# Chaoticvolt-4_digit_7seg_display.net
KiCad netlist of a schematic drawn in EasyEDA Pro
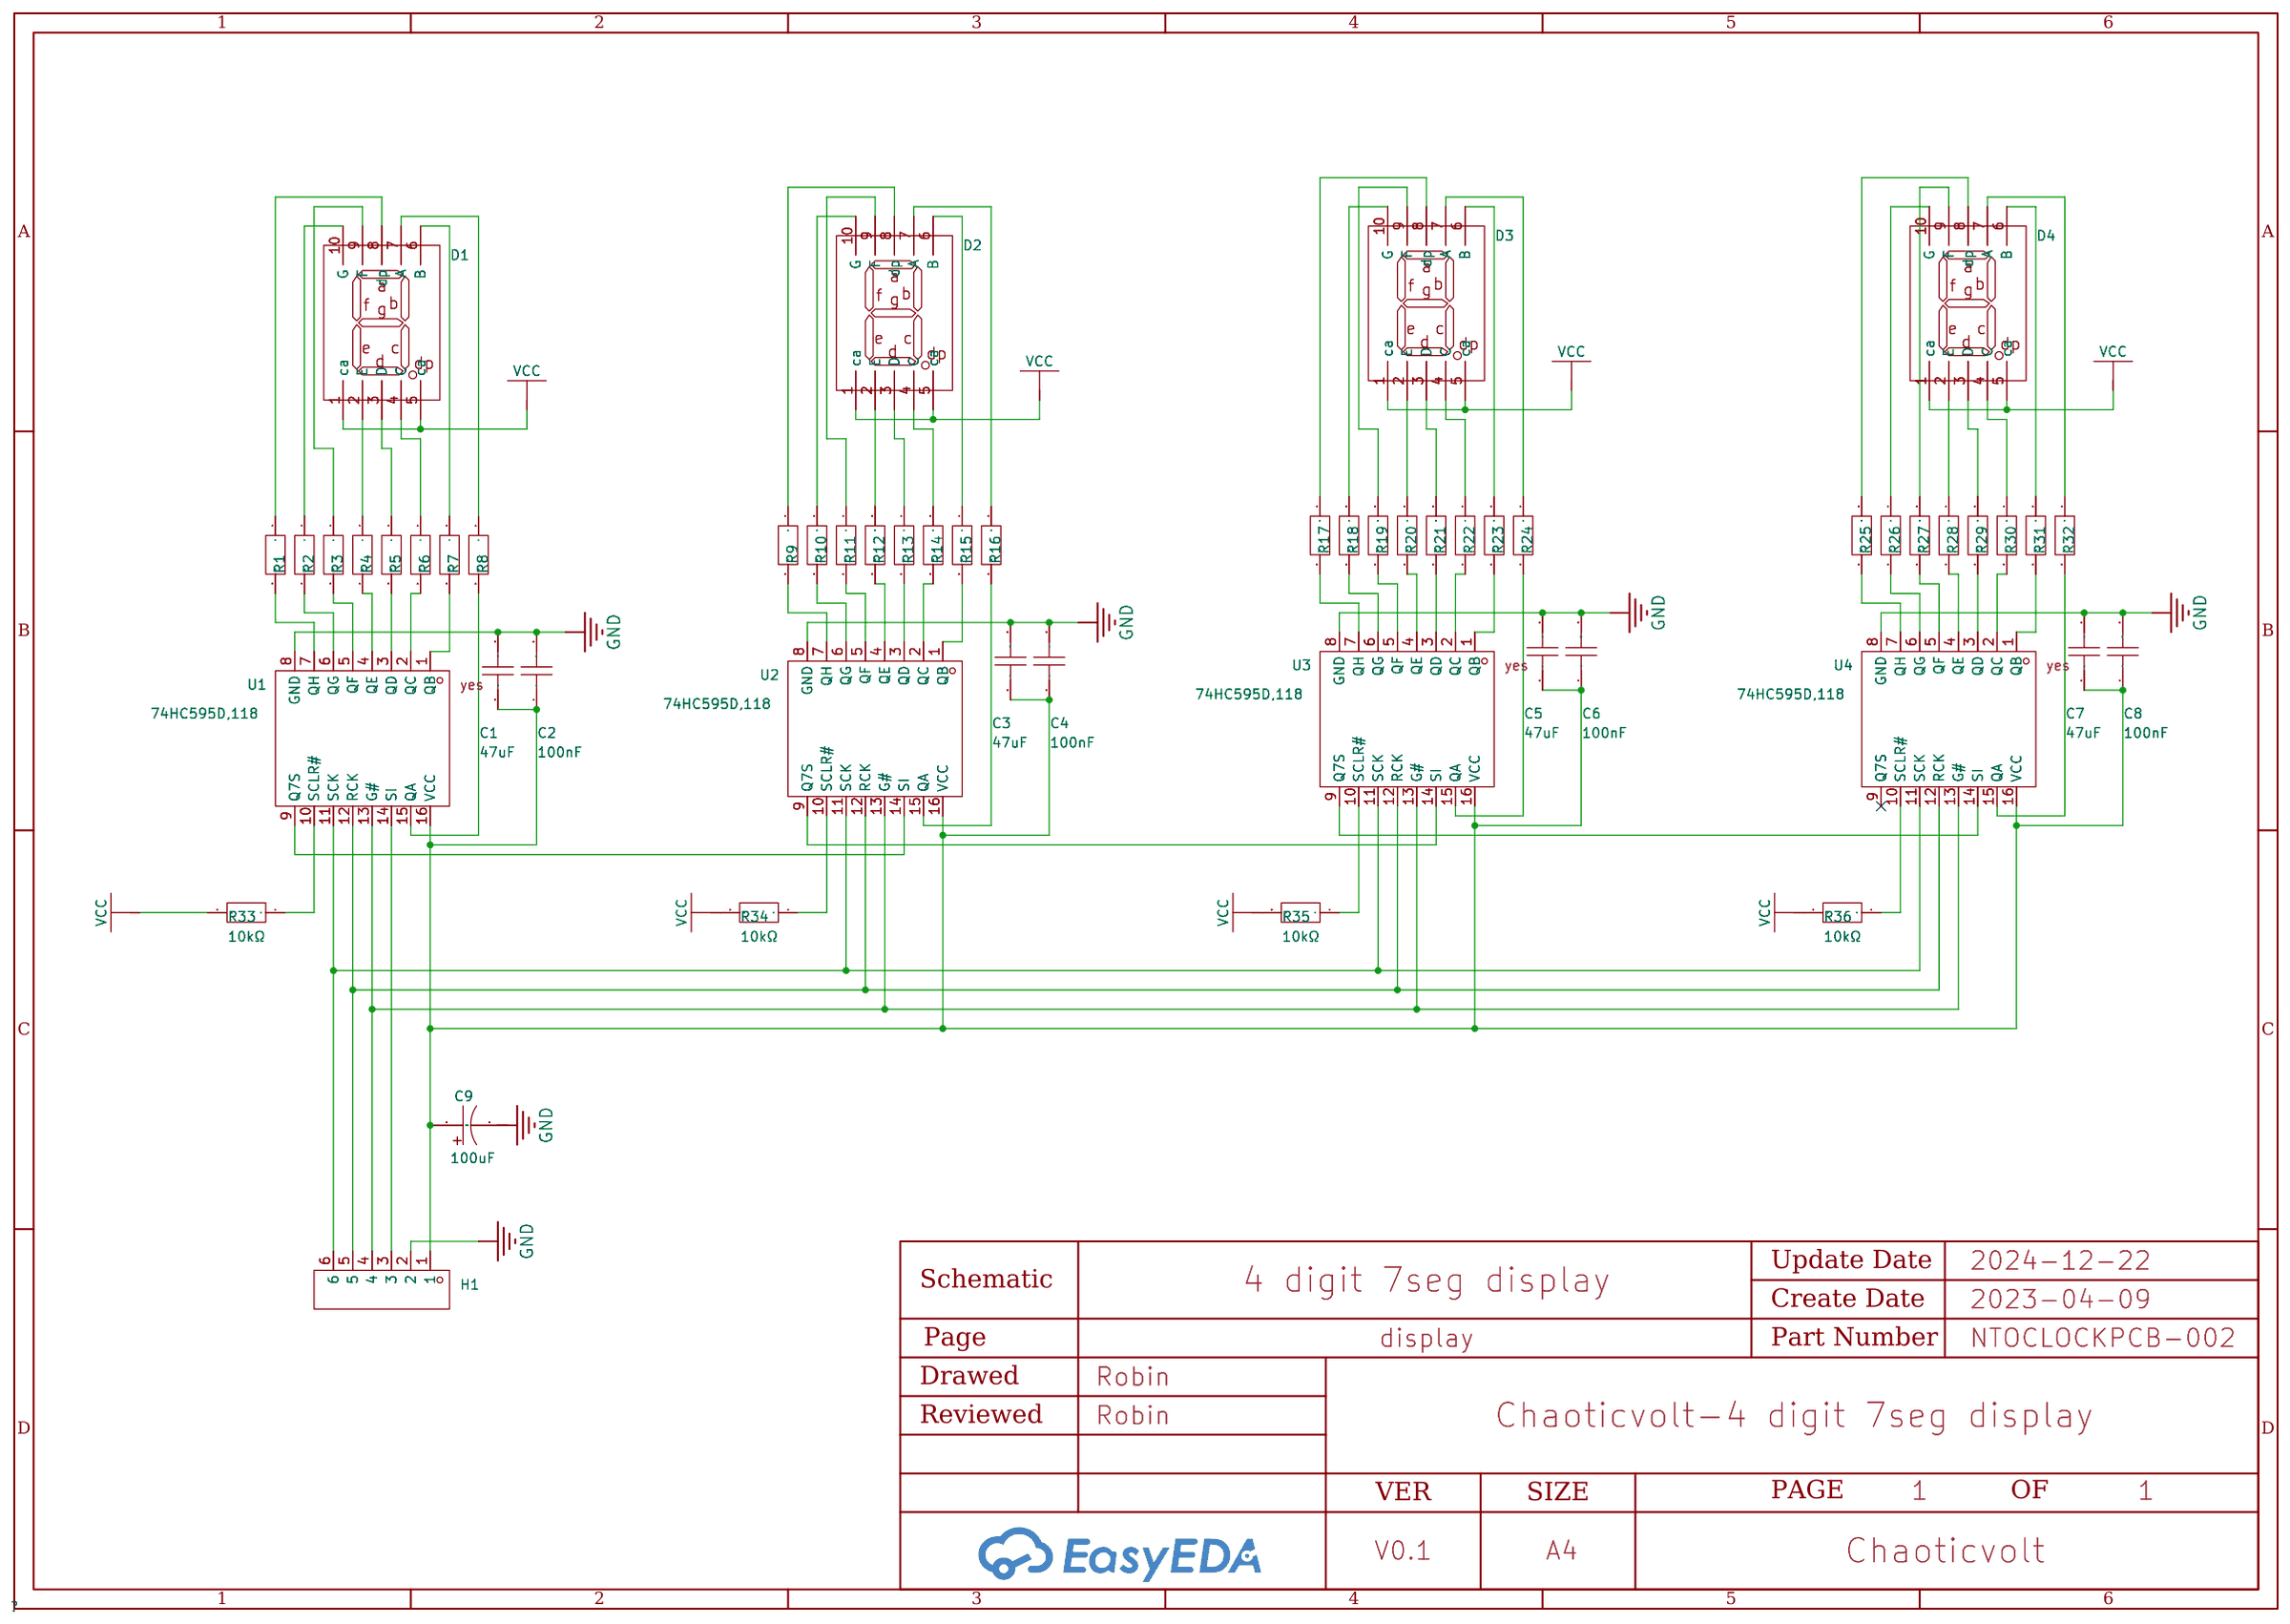
[diagram p0: schematic sheet]

(export (version "E")
  (design (tool "Eeschema 10.0.6"))
  (components
    (comp (ref "C1")
      (value "47uF")
      (footprint "easyedapro:C1206")
      (fields
        (field (name "Manufacturer Part") "CL31A476MPHNNNE")
        (field (name "Manufacturer") "SAMSUNG(三星)")
      )
      (libsource (lib "easyedapro") (part "CL31A476MPHNNNE"))
    )
    (comp (ref "C2")
      (value "100nF")
      (footprint "easyedapro:C1210")
      (fields
        (field (name "Manufacturer Part") "CL05B104KO5NNNC")
        (field (name "Manufacturer") "SAMSUNG(三星)")
      )
      (libsource (lib "easyedapro") (part "C1210C104K1RAC7800"))
    )
    (comp (ref "C3")
      (value "47uF")
      (footprint "easyedapro:C1206")
      (fields
        (field (name "Manufacturer Part") "CL31A476MPHNNNE")
        (field (name "Manufacturer") "SAMSUNG(三星)")
      )
      (libsource (lib "easyedapro") (part "CL31A476MPHNNNE"))
    )
    (comp (ref "C4")
      (value "100nF")
      (footprint "easyedapro:C1210")
      (fields
        (field (name "Manufacturer Part") "CL05B104KO5NNNC")
        (field (name "Manufacturer") "SAMSUNG(三星)")
      )
      (libsource (lib "easyedapro") (part "C1210C104K1RAC7800"))
    )
    (comp (ref "C5")
      (value "47uF")
      (footprint "easyedapro:C1206")
      (fields
        (field (name "Manufacturer Part") "CL31A476MPHNNNE")
        (field (name "Manufacturer") "SAMSUNG(三星)")
      )
      (libsource (lib "easyedapro") (part "CL31A476MPHNNNE"))
    )
    (comp (ref "C6")
      (value "100nF")
      (footprint "easyedapro:C1210")
      (fields
        (field (name "Manufacturer Part") "CL05B104KO5NNNC")
        (field (name "Manufacturer") "SAMSUNG(三星)")
      )
      (libsource (lib "easyedapro") (part "C1210C104K1RAC7800"))
    )
    (comp (ref "C7")
      (value "47uF")
      (footprint "easyedapro:C1206")
      (fields
        (field (name "Manufacturer Part") "CL31A476MPHNNNE")
        (field (name "Manufacturer") "SAMSUNG(三星)")
      )
      (libsource (lib "easyedapro") (part "CL31A476MPHNNNE"))
    )
    (comp (ref "C8")
      (value "100nF")
      (footprint "easyedapro:C1210")
      (fields
        (field (name "Manufacturer Part") "CL05B104KO5NNNC")
        (field (name "Manufacturer") "SAMSUNG(三星)")
      )
      (libsource (lib "easyedapro") (part "C1210C104K1RAC7800"))
    )
    (comp (ref "C9")
      (value "100uF")
      (footprint "easyedapro:CAP-SMD_L3.5-W2.8-R-RD")
      (fields
        (field (name "Manufacturer Part") "CA45-B-10V-100uF-M")
        (field (name "Manufacturer") "CEC(振华新云)")
      )
      (libsource (lib "easyedapro") (part "CA45-B-10V-100UF-M"))
    )
    (comp (ref "D1")
      (value "~")
      (footprint "easyedapro:FJS12101")
      (libsource (lib "easyedapro") (part "FJS12101"))
    )
    (comp (ref "D2")
      (value "~")
      (footprint "easyedapro:FJS12101")
      (libsource (lib "easyedapro") (part "FJS12101"))
    )
    (comp (ref "D3")
      (value "~")
      (footprint "easyedapro:FJS12101")
      (libsource (lib "easyedapro") (part "FJS12101"))
    )
    (comp (ref "D4")
      (value "~")
      (footprint "easyedapro:FJS12101")
      (libsource (lib "easyedapro") (part "FJS12101"))
    )
    (comp (ref "H1")
      (value "~")
      (footprint "easyedapro:HDR-TH_6P-P2.54-V_Z-211-0611-0021-001")
      (fields (field (name "Manufacturer Part") "PZ254R-11-06P") (field (name "Manufacturer") "XFCN(兴飞)"))
      (libsource (lib "easyedapro") (part "PZ254R-11-06P"))
    )
    (comp (ref "R1")
      (value "100Ω")
      (footprint "easyedapro:R1210")
      (fields
        (field (name "Manufacturer Part") "0805W8F1000T5E")
        (field (name "Manufacturer") "UNI-ROYAL(厚声)")
      )
      (libsource (lib "easyedapro") (part "RK73H2ETTD2700F"))
    )
    (comp (ref "R2")
      (value "100Ω")
      (footprint "easyedapro:R1210")
      (fields
        (field (name "Manufacturer Part") "0805W8F1000T5E")
        (field (name "Manufacturer") "UNI-ROYAL(厚声)")
      )
      (libsource (lib "easyedapro") (part "RK73H2ETTD2700F"))
    )
    (comp (ref "R3")
      (value "100Ω")
      (footprint "easyedapro:R1210")
      (fields
        (field (name "Manufacturer Part") "0805W8F1000T5E")
        (field (name "Manufacturer") "UNI-ROYAL(厚声)")
      )
      (libsource (lib "easyedapro") (part "RK73H2ETTD2700F"))
    )
    (comp (ref "R4")
      (value "100Ω")
      (footprint "easyedapro:R1210")
      (fields
        (field (name "Manufacturer Part") "0805W8F1000T5E")
        (field (name "Manufacturer") "UNI-ROYAL(厚声)")
      )
      (libsource (lib "easyedapro") (part "RK73H2ETTD2700F"))
    )
    (comp (ref "R5")
      (value "100Ω")
      (footprint "easyedapro:R1210")
      (fields
        (field (name "Manufacturer Part") "0805W8F1000T5E")
        (field (name "Manufacturer") "UNI-ROYAL(厚声)")
      )
      (libsource (lib "easyedapro") (part "RK73H2ETTD2700F"))
    )
    (comp (ref "R6")
      (value "100Ω")
      (footprint "easyedapro:R1210")
      (fields
        (field (name "Manufacturer Part") "0805W8F1000T5E")
        (field (name "Manufacturer") "UNI-ROYAL(厚声)")
      )
      (libsource (lib "easyedapro") (part "RK73H2ETTD2700F"))
    )
    (comp (ref "R7")
      (value "100Ω")
      (footprint "easyedapro:R1210")
      (fields
        (field (name "Manufacturer Part") "0805W8F1000T5E")
        (field (name "Manufacturer") "UNI-ROYAL(厚声)")
      )
      (libsource (lib "easyedapro") (part "RK73H2ETTD2700F"))
    )
    (comp (ref "R8")
      (value "100Ω")
      (footprint "easyedapro:R1210")
      (fields
        (field (name "Manufacturer Part") "0805W8F1000T5E")
        (field (name "Manufacturer") "UNI-ROYAL(厚声)")
      )
      (libsource (lib "easyedapro") (part "RK73H2ETTD2700F"))
    )
    (comp (ref "R9")
      (value "100Ω")
      (footprint "easyedapro:R1210")
      (fields
        (field (name "Manufacturer Part") "0805W8F1000T5E")
        (field (name "Manufacturer") "UNI-ROYAL(厚声)")
      )
      (libsource (lib "easyedapro") (part "RK73H2ETTD2700F"))
    )
    (comp (ref "R10")
      (value "100Ω")
      (footprint "easyedapro:R1210")
      (fields
        (field (name "Manufacturer Part") "0805W8F1000T5E")
        (field (name "Manufacturer") "UNI-ROYAL(厚声)")
      )
      (libsource (lib "easyedapro") (part "RK73H2ETTD2700F"))
    )
    (comp (ref "R11")
      (value "100Ω")
      (footprint "easyedapro:R1210")
      (fields
        (field (name "Manufacturer Part") "0805W8F1000T5E")
        (field (name "Manufacturer") "UNI-ROYAL(厚声)")
      )
      (libsource (lib "easyedapro") (part "RK73H2ETTD2700F"))
    )
    (comp (ref "R12")
      (value "100Ω")
      (footprint "easyedapro:R1210")
      (fields
        (field (name "Manufacturer Part") "0805W8F1000T5E")
        (field (name "Manufacturer") "UNI-ROYAL(厚声)")
      )
      (libsource (lib "easyedapro") (part "RK73H2ETTD2700F"))
    )
    (comp (ref "R13")
      (value "100Ω")
      (footprint "easyedapro:R1210")
      (fields
        (field (name "Manufacturer Part") "0805W8F1000T5E")
        (field (name "Manufacturer") "UNI-ROYAL(厚声)")
      )
      (libsource (lib "easyedapro") (part "RK73H2ETTD2700F"))
    )
    (comp (ref "R14")
      (value "100Ω")
      (footprint "easyedapro:R1210")
      (fields
        (field (name "Manufacturer Part") "0805W8F1000T5E")
        (field (name "Manufacturer") "UNI-ROYAL(厚声)")
      )
      (libsource (lib "easyedapro") (part "RK73H2ETTD2700F"))
    )
    (comp (ref "R15")
      (value "100Ω")
      (footprint "easyedapro:R1210")
      (fields
        (field (name "Manufacturer Part") "0805W8F1000T5E")
        (field (name "Manufacturer") "UNI-ROYAL(厚声)")
      )
      (libsource (lib "easyedapro") (part "RK73H2ETTD2700F"))
    )
    (comp (ref "R16")
      (value "100Ω")
      (footprint "easyedapro:R1210")
      (fields
        (field (name "Manufacturer Part") "0805W8F1000T5E")
        (field (name "Manufacturer") "UNI-ROYAL(厚声)")
      )
      (libsource (lib "easyedapro") (part "RK73H2ETTD2700F"))
    )
    (comp (ref "R17")
      (value "100Ω")
      (footprint "easyedapro:R1210")
      (fields
        (field (name "Manufacturer Part") "0805W8F1000T5E")
        (field (name "Manufacturer") "UNI-ROYAL(厚声)")
      )
      (libsource (lib "easyedapro") (part "RK73H2ETTD2700F"))
    )
    (comp (ref "R18")
      (value "100Ω")
      (footprint "easyedapro:R1210")
      (fields
        (field (name "Manufacturer Part") "0805W8F1000T5E")
        (field (name "Manufacturer") "UNI-ROYAL(厚声)")
      )
      (libsource (lib "easyedapro") (part "RK73H2ETTD2700F"))
    )
    (comp (ref "R19")
      (value "100Ω")
      (footprint "easyedapro:R1210")
      (fields
        (field (name "Manufacturer Part") "0805W8F1000T5E")
        (field (name "Manufacturer") "UNI-ROYAL(厚声)")
      )
      (libsource (lib "easyedapro") (part "RK73H2ETTD2700F"))
    )
    (comp (ref "R20")
      (value "100Ω")
      (footprint "easyedapro:R1210")
      (fields
        (field (name "Manufacturer Part") "0805W8F1000T5E")
        (field (name "Manufacturer") "UNI-ROYAL(厚声)")
      )
      (libsource (lib "easyedapro") (part "RK73H2ETTD2700F"))
    )
    (comp (ref "R21")
      (value "100Ω")
      (footprint "easyedapro:R1210")
      (fields
        (field (name "Manufacturer Part") "0805W8F1000T5E")
        (field (name "Manufacturer") "UNI-ROYAL(厚声)")
      )
      (libsource (lib "easyedapro") (part "RK73H2ETTD2700F"))
    )
    (comp (ref "R22")
      (value "100Ω")
      (footprint "easyedapro:R1210")
      (fields
        (field (name "Manufacturer Part") "0805W8F1000T5E")
        (field (name "Manufacturer") "UNI-ROYAL(厚声)")
      )
      (libsource (lib "easyedapro") (part "RK73H2ETTD2700F"))
    )
    (comp (ref "R23")
      (value "100Ω")
      (footprint "easyedapro:R1210")
      (fields
        (field (name "Manufacturer Part") "0805W8F1000T5E")
        (field (name "Manufacturer") "UNI-ROYAL(厚声)")
      )
      (libsource (lib "easyedapro") (part "RK73H2ETTD2700F"))
    )
    (comp (ref "R24")
      (value "100Ω")
      (footprint "easyedapro:R1210")
      (fields
        (field (name "Manufacturer Part") "0805W8F1000T5E")
        (field (name "Manufacturer") "UNI-ROYAL(厚声)")
      )
      (libsource (lib "easyedapro") (part "RK73H2ETTD2700F"))
    )
    (comp (ref "R25")
      (value "100Ω")
      (footprint "easyedapro:R1210")
      (fields
        (field (name "Manufacturer Part") "0805W8F1000T5E")
        (field (name "Manufacturer") "UNI-ROYAL(厚声)")
      )
      (libsource (lib "easyedapro") (part "RK73H2ETTD2700F"))
    )
    (comp (ref "R26")
      (value "100Ω")
      (footprint "easyedapro:R1210")
      (fields
        (field (name "Manufacturer Part") "0805W8F1000T5E")
        (field (name "Manufacturer") "UNI-ROYAL(厚声)")
      )
      (libsource (lib "easyedapro") (part "RK73H2ETTD2700F"))
    )
    (comp (ref "R27")
      (value "100Ω")
      (footprint "easyedapro:R1210")
      (fields
        (field (name "Manufacturer Part") "0805W8F1000T5E")
        (field (name "Manufacturer") "UNI-ROYAL(厚声)")
      )
      (libsource (lib "easyedapro") (part "RK73H2ETTD2700F"))
    )
    (comp (ref "R28")
      (value "100Ω")
      (footprint "easyedapro:R1210")
      (fields
        (field (name "Manufacturer Part") "0805W8F1000T5E")
        (field (name "Manufacturer") "UNI-ROYAL(厚声)")
      )
      (libsource (lib "easyedapro") (part "RK73H2ETTD2700F"))
    )
    (comp (ref "R29")
      (value "100Ω")
      (footprint "easyedapro:R1210")
      (fields
        (field (name "Manufacturer Part") "0805W8F1000T5E")
        (field (name "Manufacturer") "UNI-ROYAL(厚声)")
      )
      (libsource (lib "easyedapro") (part "RK73H2ETTD2700F"))
    )
    (comp (ref "R30")
      (value "100Ω")
      (footprint "easyedapro:R1210")
      (fields
        (field (name "Manufacturer Part") "0805W8F1000T5E")
        (field (name "Manufacturer") "UNI-ROYAL(厚声)")
      )
      (libsource (lib "easyedapro") (part "RK73H2ETTD2700F"))
    )
    (comp (ref "R31")
      (value "100Ω")
      (footprint "easyedapro:R1210")
      (fields
        (field (name "Manufacturer Part") "0805W8F1000T5E")
        (field (name "Manufacturer") "UNI-ROYAL(厚声)")
      )
      (libsource (lib "easyedapro") (part "RK73H2ETTD2700F"))
    )
    (comp (ref "R32")
      (value "100Ω")
      (footprint "easyedapro:R1210")
      (fields
        (field (name "Manufacturer Part") "0805W8F1000T5E")
        (field (name "Manufacturer") "UNI-ROYAL(厚声)")
      )
      (libsource (lib "easyedapro") (part "RK73H2ETTD2700F"))
    )
    (comp (ref "R33")
      (value "10kΩ")
      (footprint "easyedapro:R1210")
      (fields
        (field (name "Manufacturer Part") "0805W8F1002T5E")
        (field (name "Manufacturer") "UNI-ROYAL(厚声)")
      )
      (libsource (lib "easyedapro") (part "RK73H2ETTD1002F"))
    )
    (comp (ref "R34")
      (value "10kΩ")
      (footprint "easyedapro:R1210")
      (fields
        (field (name "Manufacturer Part") "0805W8F1002T5E")
        (field (name "Manufacturer") "UNI-ROYAL(厚声)")
      )
      (libsource (lib "easyedapro") (part "RK73H2ETTD1002F"))
    )
    (comp (ref "R35")
      (value "10kΩ")
      (footprint "easyedapro:R1210")
      (fields
        (field (name "Manufacturer Part") "0805W8F1002T5E")
        (field (name "Manufacturer") "UNI-ROYAL(厚声)")
      )
      (libsource (lib "easyedapro") (part "RK73H2ETTD1002F"))
    )
    (comp (ref "R36")
      (value "10kΩ")
      (footprint "easyedapro:R1210")
      (fields
        (field (name "Manufacturer Part") "0805W8F1002T5E")
        (field (name "Manufacturer") "UNI-ROYAL(厚声)")
      )
      (libsource (lib "easyedapro") (part "RK73H2ETTD1002F"))
    )
    (comp (ref "U1")
      (value "74HC595D,118")
      (footprint "easyedapro:SOIC-16_L9.9-W3.9-P1.27-LS6.0-BL")
      (fields (field (name "Manufacturer") "Nexperia(安世)") (field (name "Add into BOM") "yes"))
      (libsource (lib "easyedapro") (part "74HC595D_C431479"))
    )
    (comp (ref "U2")
      (value "74HC595D,118")
      (footprint "easyedapro:SOIC-16_L9.9-W3.9-P1.27-LS6.0-BL")
      (fields (field (name "Manufacturer") "Nexperia(安世)"))
      (libsource (lib "easyedapro") (part "74HC595D_C431479"))
    )
    (comp (ref "U3")
      (value "74HC595D,118")
      (footprint "easyedapro:SOIC-16_L9.9-W3.9-P1.27-LS6.0-BL")
      (fields (field (name "Manufacturer") "Nexperia(安世)") (field (name "Add into BOM") "yes"))
      (libsource (lib "easyedapro") (part "74HC595D_C431479"))
    )
    (comp (ref "U4")
      (value "74HC595D,118")
      (footprint "easyedapro:SOIC-16_L9.9-W3.9-P1.27-LS6.0-BL")
      (fields (field (name "Manufacturer") "Nexperia(安世)") (field (name "Add into BOM") "yes"))
      (libsource (lib "easyedapro") (part "74HC595D_C431479"))
    )
  )
  (nets
    (net (code "1") (name "GND") (class "Default")
      (node (ref "C1") (pin "2") (pinfunction "2_2") (pintype "input"))
      (node (ref "C2") (pin "2") (pinfunction "2_2") (pintype "input"))
      (node (ref "C3") (pin "2") (pinfunction "2_2") (pintype "input"))
      (node (ref "C4") (pin "2") (pinfunction "2_2") (pintype "input"))
      (node (ref "C5") (pin "2") (pinfunction "2_2") (pintype "input"))
      (node (ref "C6") (pin "2") (pinfunction "2_2") (pintype "input"))
      (node (ref "C7") (pin "2") (pinfunction "2_2") (pintype "input"))
      (node (ref "C8") (pin "2") (pinfunction "2_2") (pintype "input"))
      (node (ref "C9") (pin "2") (pinfunction "2_2") (pintype "input"))
      (node (ref "H1") (pin "2") (pinfunction "2_2") (pintype "input"))
      (node (ref "U1") (pin "8") (pinfunction "GND_8") (pintype "input"))
      (node (ref "U2") (pin "8") (pinfunction "GND_8") (pintype "input"))
      (node (ref "U3") (pin "8") (pinfunction "GND_8") (pintype "input"))
      (node (ref "U4") (pin "8") (pinfunction "GND_8") (pintype "input"))
    )
    (net (code "2") (name "Net-(D1-A)") (class "Default")
      (node (ref "D1") (pin "7") (pinfunction "A_7") (pintype "input"))
      (node (ref "R8") (pin "1") (pinfunction "1_1") (pintype "input"))
    )
    (net (code "3") (name "Net-(D1-B)") (class "Default")
      (node (ref "D1") (pin "6") (pinfunction "B_6") (pintype "input"))
      (node (ref "R7") (pin "1") (pinfunction "1_1") (pintype "input"))
    )
    (net (code "4") (name "Net-(D1-C)") (class "Default")
      (node (ref "D1") (pin "4") (pinfunction "C_4") (pintype "input"))
      (node (ref "R6") (pin "1") (pinfunction "1_1") (pintype "input"))
    )
    (net (code "5") (name "Net-(D1-D)") (class "Default")
      (node (ref "D1") (pin "3") (pinfunction "D_3") (pintype "input"))
      (node (ref "R5") (pin "1") (pinfunction "1_1") (pintype "input"))
    )
    (net (code "6") (name "Net-(D1-E)") (class "Default")
      (node (ref "D1") (pin "2") (pinfunction "E_2") (pintype "input"))
      (node (ref "R4") (pin "1") (pinfunction "1_1") (pintype "input"))
    )
    (net (code "7") (name "Net-(D1-F)") (class "Default")
      (node (ref "D1") (pin "9") (pinfunction "F_9") (pintype "input"))
      (node (ref "R3") (pin "1") (pinfunction "1_1") (pintype "input"))
    )
    (net (code "8") (name "Net-(D1-G)") (class "Default")
      (node (ref "D1") (pin "10") (pinfunction "G_10") (pintype "input"))
      (node (ref "R2") (pin "1") (pinfunction "1_1") (pintype "input"))
    )
    (net (code "9") (name "Net-(D1-dp)") (class "Default")
      (node (ref "D1") (pin "8") (pinfunction "dp_8") (pintype "input"))
      (node (ref "R1") (pin "1") (pinfunction "1_1") (pintype "input"))
    )
    (net (code "10") (name "Net-(D2-A)") (class "Default")
      (node (ref "D2") (pin "7") (pinfunction "A_7") (pintype "input"))
      (node (ref "R16") (pin "1") (pinfunction "1_1") (pintype "input"))
    )
    (net (code "11") (name "Net-(D2-B)") (class "Default")
      (node (ref "D2") (pin "6") (pinfunction "B_6") (pintype "input"))
      (node (ref "R15") (pin "1") (pinfunction "1_1") (pintype "input"))
    )
    (net (code "12") (name "Net-(D2-C)") (class "Default")
      (node (ref "D2") (pin "4") (pinfunction "C_4") (pintype "input"))
      (node (ref "R14") (pin "1") (pinfunction "1_1") (pintype "input"))
    )
    (net (code "13") (name "Net-(D2-D)") (class "Default")
      (node (ref "D2") (pin "3") (pinfunction "D_3") (pintype "input"))
      (node (ref "R13") (pin "1") (pinfunction "1_1") (pintype "input"))
    )
    (net (code "14") (name "Net-(D2-E)") (class "Default")
      (node (ref "D2") (pin "2") (pinfunction "E_2") (pintype "input"))
      (node (ref "R12") (pin "1") (pinfunction "1_1") (pintype "input"))
    )
    (net (code "15") (name "Net-(D2-F)") (class "Default")
      (node (ref "D2") (pin "9") (pinfunction "F_9") (pintype "input"))
      (node (ref "R11") (pin "1") (pinfunction "1_1") (pintype "input"))
    )
    (net (code "16") (name "Net-(D2-G)") (class "Default")
      (node (ref "D2") (pin "10") (pinfunction "G_10") (pintype "input"))
      (node (ref "R10") (pin "1") (pinfunction "1_1") (pintype "input"))
    )
    (net (code "17") (name "Net-(D2-dp)") (class "Default")
      (node (ref "D2") (pin "8") (pinfunction "dp_8") (pintype "input"))
      (node (ref "R9") (pin "1") (pinfunction "1_1") (pintype "input"))
    )
    (net (code "18") (name "Net-(D3-A)") (class "Default")
      (node (ref "D3") (pin "7") (pinfunction "A_7") (pintype "input"))
      (node (ref "R24") (pin "1") (pinfunction "1_1") (pintype "input"))
    )
    (net (code "19") (name "Net-(D3-B)") (class "Default")
      (node (ref "D3") (pin "6") (pinfunction "B_6") (pintype "input"))
      (node (ref "R23") (pin "1") (pinfunction "1_1") (pintype "input"))
    )
    (net (code "20") (name "Net-(D3-C)") (class "Default")
      (node (ref "D3") (pin "4") (pinfunction "C_4") (pintype "input"))
      (node (ref "R22") (pin "1") (pinfunction "1_1") (pintype "input"))
    )
    (net (code "21") (name "Net-(D3-D)") (class "Default")
      (node (ref "D3") (pin "3") (pinfunction "D_3") (pintype "input"))
      (node (ref "R21") (pin "1") (pinfunction "1_1") (pintype "input"))
    )
    (net (code "22") (name "Net-(D3-E)") (class "Default")
      (node (ref "D3") (pin "2") (pinfunction "E_2") (pintype "input"))
      (node (ref "R20") (pin "1") (pinfunction "1_1") (pintype "input"))
    )
    (net (code "23") (name "Net-(D3-F)") (class "Default")
      (node (ref "D3") (pin "9") (pinfunction "F_9") (pintype "input"))
      (node (ref "R19") (pin "1") (pinfunction "1_1") (pintype "input"))
    )
    (net (code "24") (name "Net-(D3-G)") (class "Default")
      (node (ref "D3") (pin "10") (pinfunction "G_10") (pintype "input"))
      (node (ref "R18") (pin "1") (pinfunction "1_1") (pintype "input"))
    )
    (net (code "25") (name "Net-(D3-dp)") (class "Default")
      (node (ref "D3") (pin "8") (pinfunction "dp_8") (pintype "input"))
      (node (ref "R17") (pin "1") (pinfunction "1_1") (pintype "input"))
    )
    (net (code "26") (name "Net-(D4-A)") (class "Default")
      (node (ref "D4") (pin "7") (pinfunction "A_7") (pintype "input"))
      (node (ref "R32") (pin "1") (pinfunction "1_1") (pintype "input"))
    )
    (net (code "27") (name "Net-(D4-B)") (class "Default")
      (node (ref "D4") (pin "6") (pinfunction "B_6") (pintype "input"))
      (node (ref "R31") (pin "1") (pinfunction "1_1") (pintype "input"))
    )
    (net (code "28") (name "Net-(D4-C)") (class "Default")
      (node (ref "D4") (pin "4") (pinfunction "C_4") (pintype "input"))
      (node (ref "R30") (pin "1") (pinfunction "1_1") (pintype "input"))
    )
    (net (code "29") (name "Net-(D4-D)") (class "Default")
      (node (ref "D4") (pin "3") (pinfunction "D_3") (pintype "input"))
      (node (ref "R29") (pin "1") (pinfunction "1_1") (pintype "input"))
    )
    (net (code "30") (name "Net-(D4-E)") (class "Default")
      (node (ref "D4") (pin "2") (pinfunction "E_2") (pintype "input"))
      (node (ref "R28") (pin "1") (pinfunction "1_1") (pintype "input"))
    )
    (net (code "31") (name "Net-(D4-F)") (class "Default")
      (node (ref "D4") (pin "9") (pinfunction "F_9") (pintype "input"))
      (node (ref "R27") (pin "1") (pinfunction "1_1") (pintype "input"))
    )
    (net (code "32") (name "Net-(D4-G)") (class "Default")
      (node (ref "D4") (pin "10") (pinfunction "G_10") (pintype "input"))
      (node (ref "R26") (pin "1") (pinfunction "1_1") (pintype "input"))
    )
    (net (code "33") (name "Net-(D4-dp)") (class "Default")
      (node (ref "D4") (pin "8") (pinfunction "dp_8") (pintype "input"))
      (node (ref "R25") (pin "1") (pinfunction "1_1") (pintype "input"))
    )
    (net (code "34") (name "Net-(U1-G#)") (class "Default")
      (node (ref "H1") (pin "4") (pinfunction "4_4") (pintype "input"))
      (node (ref "U1") (pin "13") (pinfunction "G#_13") (pintype "input"))
      (node (ref "U2") (pin "13") (pinfunction "G#_13") (pintype "input"))
      (node (ref "U3") (pin "13") (pinfunction "G#_13") (pintype "input"))
      (node (ref "U4") (pin "13") (pinfunction "G#_13") (pintype "input"))
    )
    (net (code "35") (name "Net-(U1-Q7S)") (class "Default")
      (node (ref "U1") (pin "9") (pinfunction "Q7S_9") (pintype "input"))
      (node (ref "U2") (pin "14") (pinfunction "SI_14") (pintype "input"))
    )
    (net (code "36") (name "Net-(U1-QA)") (class "Default")
      (node (ref "R8") (pin "2") (pinfunction "2_2") (pintype "input"))
      (node (ref "U1") (pin "15") (pinfunction "QA_15") (pintype "input"))
    )
    (net (code "37") (name "Net-(U1-QB)") (class "Default")
      (node (ref "R7") (pin "2") (pinfunction "2_2") (pintype "input"))
      (node (ref "U1") (pin "1") (pinfunction "QB_1") (pintype "input"))
    )
    (net (code "38") (name "Net-(U1-QC)") (class "Default")
      (node (ref "R6") (pin "2") (pinfunction "2_2") (pintype "input"))
      (node (ref "U1") (pin "2") (pinfunction "QC_2") (pintype "input"))
    )
    (net (code "39") (name "Net-(U1-QD)") (class "Default")
      (node (ref "R5") (pin "2") (pinfunction "2_2") (pintype "input"))
      (node (ref "U1") (pin "3") (pinfunction "QD_3") (pintype "input"))
    )
    (net (code "40") (name "Net-(U1-QE)") (class "Default")
      (node (ref "R4") (pin "2") (pinfunction "2_2") (pintype "input"))
      (node (ref "U1") (pin "4") (pinfunction "QE_4") (pintype "input"))
    )
    (net (code "41") (name "Net-(U1-QF)") (class "Default")
      (node (ref "R3") (pin "2") (pinfunction "2_2") (pintype "input"))
      (node (ref "U1") (pin "5") (pinfunction "QF_5") (pintype "input"))
    )
    (net (code "42") (name "Net-(U1-QG)") (class "Default")
      (node (ref "R2") (pin "2") (pinfunction "2_2") (pintype "input"))
      (node (ref "U1") (pin "6") (pinfunction "QG_6") (pintype "input"))
    )
    (net (code "43") (name "Net-(U1-QH)") (class "Default")
      (node (ref "R1") (pin "2") (pinfunction "2_2") (pintype "input"))
      (node (ref "U1") (pin "7") (pinfunction "QH_7") (pintype "input"))
    )
    (net (code "44") (name "Net-(U1-RCK)") (class "Default")
      (node (ref "H1") (pin "5") (pinfunction "5_5") (pintype "input"))
      (node (ref "U1") (pin "12") (pinfunction "RCK_12") (pintype "input"))
      (node (ref "U2") (pin "12") (pinfunction "RCK_12") (pintype "input"))
      (node (ref "U3") (pin "12") (pinfunction "RCK_12") (pintype "input"))
      (node (ref "U4") (pin "12") (pinfunction "RCK_12") (pintype "input"))
    )
    (net (code "45") (name "Net-(U1-SCK)") (class "Default")
      (node (ref "H1") (pin "6") (pinfunction "6_6") (pintype "input"))
      (node (ref "U1") (pin "11") (pinfunction "SCK_11") (pintype "input"))
      (node (ref "U2") (pin "11") (pinfunction "SCK_11") (pintype "input"))
      (node (ref "U3") (pin "11") (pinfunction "SCK_11") (pintype "input"))
      (node (ref "U4") (pin "11") (pinfunction "SCK_11") (pintype "input"))
    )
    (net (code "46") (name "Net-(U1-SCLR#)") (class "Default")
      (node (ref "R33") (pin "1") (pinfunction "1_1") (pintype "input"))
      (node (ref "U1") (pin "10") (pinfunction "SCLR#_10") (pintype "input"))
    )
    (net (code "47") (name "Net-(U1-SI)") (class "Default")
      (node (ref "H1") (pin "3") (pinfunction "3_3") (pintype "input"))
      (node (ref "U1") (pin "14") (pinfunction "SI_14") (pintype "input"))
    )
    (net (code "48") (name "Net-(U1-VCC)") (class "Default")
      (node (ref "C1") (pin "1") (pinfunction "1_1") (pintype "input"))
      (node (ref "C2") (pin "1") (pinfunction "1_1") (pintype "input"))
      (node (ref "C3") (pin "1") (pinfunction "1_1") (pintype "input"))
      (node (ref "C4") (pin "1") (pinfunction "1_1") (pintype "input"))
      (node (ref "C5") (pin "1") (pinfunction "1_1") (pintype "input"))
      (node (ref "C6") (pin "1") (pinfunction "1_1") (pintype "input"))
      (node (ref "C7") (pin "1") (pinfunction "1_1") (pintype "input"))
      (node (ref "C8") (pin "1") (pinfunction "1_1") (pintype "input"))
      (node (ref "C9") (pin "1") (pinfunction "1_1") (pintype "input"))
      (node (ref "H1") (pin "1") (pinfunction "1_1") (pintype "input"))
      (node (ref "U1") (pin "16") (pinfunction "VCC_16") (pintype "input"))
      (node (ref "U2") (pin "16") (pinfunction "VCC_16") (pintype "input"))
      (node (ref "U3") (pin "16") (pinfunction "VCC_16") (pintype "input"))
      (node (ref "U4") (pin "16") (pinfunction "VCC_16") (pintype "input"))
    )
    (net (code "49") (name "Net-(U2-Q7S)") (class "Default")
      (node (ref "U2") (pin "9") (pinfunction "Q7S_9") (pintype "input"))
      (node (ref "U3") (pin "14") (pinfunction "SI_14") (pintype "input"))
    )
    (net (code "50") (name "Net-(U2-QA)") (class "Default")
      (node (ref "R16") (pin "2") (pinfunction "2_2") (pintype "input"))
      (node (ref "U2") (pin "15") (pinfunction "QA_15") (pintype "input"))
    )
    (net (code "51") (name "Net-(U2-QB)") (class "Default")
      (node (ref "R15") (pin "2") (pinfunction "2_2") (pintype "input"))
      (node (ref "U2") (pin "1") (pinfunction "QB_1") (pintype "input"))
    )
    (net (code "52") (name "Net-(U2-QC)") (class "Default")
      (node (ref "R14") (pin "2") (pinfunction "2_2") (pintype "input"))
      (node (ref "U2") (pin "2") (pinfunction "QC_2") (pintype "input"))
    )
    (net (code "53") (name "Net-(U2-QD)") (class "Default")
      (node (ref "R13") (pin "2") (pinfunction "2_2") (pintype "input"))
      (node (ref "U2") (pin "3") (pinfunction "QD_3") (pintype "input"))
    )
    (net (code "54") (name "Net-(U2-QE)") (class "Default")
      (node (ref "R12") (pin "2") (pinfunction "2_2") (pintype "input"))
      (node (ref "U2") (pin "4") (pinfunction "QE_4") (pintype "input"))
    )
    (net (code "55") (name "Net-(U2-QF)") (class "Default")
      (node (ref "R11") (pin "2") (pinfunction "2_2") (pintype "input"))
      (node (ref "U2") (pin "5") (pinfunction "QF_5") (pintype "input"))
    )
    (net (code "56") (name "Net-(U2-QG)") (class "Default")
      (node (ref "R10") (pin "2") (pinfunction "2_2") (pintype "input"))
      (node (ref "U2") (pin "6") (pinfunction "QG_6") (pintype "input"))
    )
    (net (code "57") (name "Net-(U2-QH)") (class "Default")
      (node (ref "R9") (pin "2") (pinfunction "2_2") (pintype "input"))
      (node (ref "U2") (pin "7") (pinfunction "QH_7") (pintype "input"))
    )
    (net (code "58") (name "Net-(U2-SCLR#)") (class "Default")
      (node (ref "R34") (pin "1") (pinfunction "1_1") (pintype "input"))
      (node (ref "U2") (pin "10") (pinfunction "SCLR#_10") (pintype "input"))
    )
    (net (code "59") (name "Net-(U3-Q7S)") (class "Default")
      (node (ref "U3") (pin "9") (pinfunction "Q7S_9") (pintype "input"))
      (node (ref "U4") (pin "14") (pinfunction "SI_14") (pintype "input"))
    )
    (net (code "60") (name "Net-(U3-QA)") (class "Default")
      (node (ref "R24") (pin "2") (pinfunction "2_2") (pintype "input"))
      (node (ref "U3") (pin "15") (pinfunction "QA_15") (pintype "input"))
    )
    (net (code "61") (name "Net-(U3-QB)") (class "Default")
      (node (ref "R23") (pin "2") (pinfunction "2_2") (pintype "input"))
      (node (ref "U3") (pin "1") (pinfunction "QB_1") (pintype "input"))
    )
    (net (code "62") (name "Net-(U3-QC)") (class "Default")
      (node (ref "R22") (pin "2") (pinfunction "2_2") (pintype "input"))
      (node (ref "U3") (pin "2") (pinfunction "QC_2") (pintype "input"))
    )
    (net (code "63") (name "Net-(U3-QD)") (class "Default")
      (node (ref "R21") (pin "2") (pinfunction "2_2") (pintype "input"))
      (node (ref "U3") (pin "3") (pinfunction "QD_3") (pintype "input"))
    )
    (net (code "64") (name "Net-(U3-QE)") (class "Default")
      (node (ref "R20") (pin "2") (pinfunction "2_2") (pintype "input"))
      (node (ref "U3") (pin "4") (pinfunction "QE_4") (pintype "input"))
    )
    (net (code "65") (name "Net-(U3-QF)") (class "Default")
      (node (ref "R19") (pin "2") (pinfunction "2_2") (pintype "input"))
      (node (ref "U3") (pin "5") (pinfunction "QF_5") (pintype "input"))
    )
    (net (code "66") (name "Net-(U3-QG)") (class "Default")
      (node (ref "R18") (pin "2") (pinfunction "2_2") (pintype "input"))
      (node (ref "U3") (pin "6") (pinfunction "QG_6") (pintype "input"))
    )
    (net (code "67") (name "Net-(U3-QH)") (class "Default")
      (node (ref "R17") (pin "2") (pinfunction "2_2") (pintype "input"))
      (node (ref "U3") (pin "7") (pinfunction "QH_7") (pintype "input"))
    )
    (net (code "68") (name "Net-(U3-SCLR#)") (class "Default")
      (node (ref "R35") (pin "1") (pinfunction "1_1") (pintype "input"))
      (node (ref "U3") (pin "10") (pinfunction "SCLR#_10") (pintype "input"))
    )
    (net (code "69") (name "Net-(U4-QA)") (class "Default")
      (node (ref "R32") (pin "2") (pinfunction "2_2") (pintype "input"))
      (node (ref "U4") (pin "15") (pinfunction "QA_15") (pintype "input"))
    )
    (net (code "70") (name "Net-(U4-QB)") (class "Default")
      (node (ref "R31") (pin "2") (pinfunction "2_2") (pintype "input"))
      (node (ref "U4") (pin "1") (pinfunction "QB_1") (pintype "input"))
    )
    (net (code "71") (name "Net-(U4-QC)") (class "Default")
      (node (ref "R30") (pin "2") (pinfunction "2_2") (pintype "input"))
      (node (ref "U4") (pin "2") (pinfunction "QC_2") (pintype "input"))
    )
    (net (code "72") (name "Net-(U4-QD)") (class "Default")
      (node (ref "R29") (pin "2") (pinfunction "2_2") (pintype "input"))
      (node (ref "U4") (pin "3") (pinfunction "QD_3") (pintype "input"))
    )
    (net (code "73") (name "Net-(U4-QE)") (class "Default")
      (node (ref "R28") (pin "2") (pinfunction "2_2") (pintype "input"))
      (node (ref "U4") (pin "4") (pinfunction "QE_4") (pintype "input"))
    )
    (net (code "74") (name "Net-(U4-QF)") (class "Default")
      (node (ref "R27") (pin "2") (pinfunction "2_2") (pintype "input"))
      (node (ref "U4") (pin "5") (pinfunction "QF_5") (pintype "input"))
    )
    (net (code "75") (name "Net-(U4-QG)") (class "Default")
      (node (ref "R26") (pin "2") (pinfunction "2_2") (pintype "input"))
      (node (ref "U4") (pin "6") (pinfunction "QG_6") (pintype "input"))
    )
    (net (code "76") (name "Net-(U4-QH)") (class "Default")
      (node (ref "R25") (pin "2") (pinfunction "2_2") (pintype "input"))
      (node (ref "U4") (pin "7") (pinfunction "QH_7") (pintype "input"))
    )
    (net (code "77") (name "Net-(U4-SCLR#)") (class "Default")
      (node (ref "R36") (pin "1") (pinfunction "1_1") (pintype "input"))
      (node (ref "U4") (pin "10") (pinfunction "SCLR#_10") (pintype "input"))
    )
    (net (code "78") (name "VCC") (class "Default")
      (node (ref "D1") (pin "1") (pinfunction "ca_1") (pintype "input"))
      (node (ref "D1") (pin "5") (pinfunction "ca_5") (pintype "input"))
      (node (ref "D2") (pin "1") (pinfunction "ca_1") (pintype "input"))
      (node (ref "D2") (pin "5") (pinfunction "ca_5") (pintype "input"))
      (node (ref "D3") (pin "1") (pinfunction "ca_1") (pintype "input"))
      (node (ref "D3") (pin "5") (pinfunction "ca_5") (pintype "input"))
      (node (ref "D4") (pin "1") (pinfunction "ca_1") (pintype "input"))
      (node (ref "D4") (pin "5") (pinfunction "ca_5") (pintype "input"))
      (node (ref "R33") (pin "2") (pinfunction "2_2") (pintype "input"))
      (node (ref "R34") (pin "2") (pinfunction "2_2") (pintype "input"))
      (node (ref "R35") (pin "2") (pinfunction "2_2") (pintype "input"))
      (node (ref "R36") (pin "2") (pinfunction "2_2") (pintype "input"))
    )
    (net (code "79") (name "unconnected-(U4-Q7S-Pad9)") (class "Default")
      (node (ref "U4") (pin "9") (pinfunction "Q7S_9") (pintype "input+no_connect"))
    )
  )
)
